# Isolation.net
KiCad netlist of a schematic drawn in Altium Designer
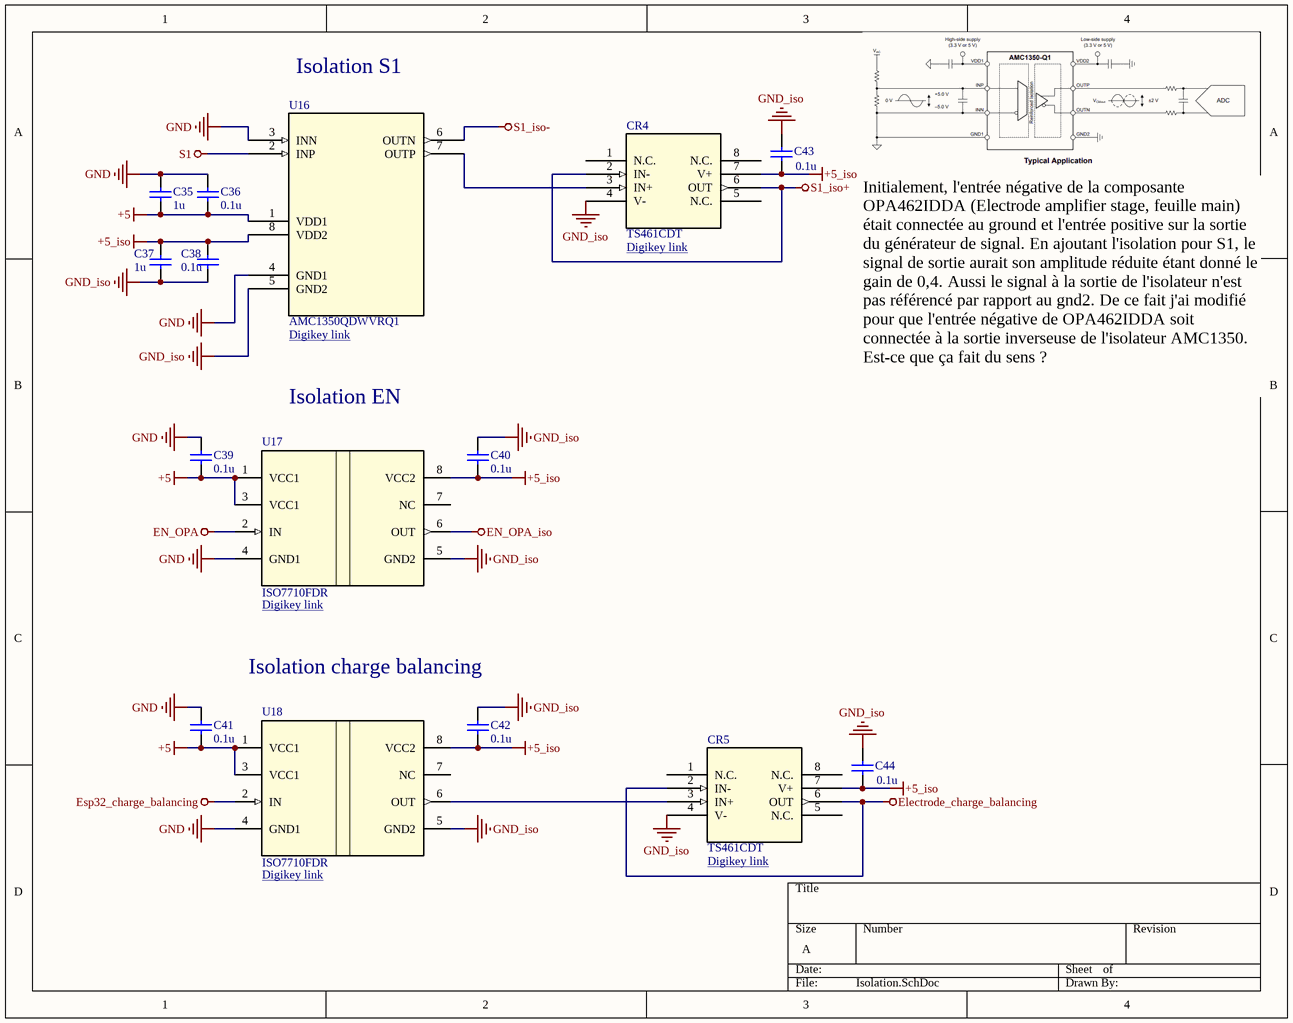
[diagram p0: Isolation.SchDoc]

(export (version "E")
  (design (tool "Eeschema 10.0.6"))
  (components
    (comp (ref "C35")
      (value "1u")
      (footprint "0805_AVX")
      (description "Capacitor")
      (libsource (lib "Simulation Generic Components") (part "Capacitor"))
    )
    (comp (ref "C36")
      (value "0.1u")
      (footprint "CAPC2012X150N")
      (description "Capacitor")
      (libsource (lib "Simulation Generic Components") (part "Capacitor"))
    )
    (comp (ref "C37")
      (value "1u")
      (footprint "0805_AVX")
      (description "Capacitor")
      (libsource (lib "Simulation Generic Components") (part "Capacitor"))
    )
    (comp (ref "C38")
      (value "0.1u")
      (footprint "CAPC2012X150N")
      (description "Capacitor")
      (libsource (lib "Simulation Generic Components") (part "Capacitor"))
    )
    (comp (ref "C39")
      (value "0.1u")
      (footprint "CAPC2012X150N")
      (description "Capacitor")
      (libsource (lib "Simulation Generic Components") (part "Capacitor"))
    )
    (comp (ref "C40")
      (value "0.1u")
      (footprint "CAPC2012X150N")
      (description "Capacitor")
      (libsource (lib "Simulation Generic Components") (part "Capacitor"))
    )
    (comp (ref "C41")
      (value "0.1u")
      (footprint "CAPC2012X150N")
      (description "Capacitor")
      (libsource (lib "Simulation Generic Components") (part "Capacitor"))
    )
    (comp (ref "C42")
      (value "0.1u")
      (footprint "CAPC2012X150N")
      (description "Capacitor")
      (libsource (lib "Simulation Generic Components") (part "Capacitor"))
    )
    (comp (ref "C43")
      (value "0.1u")
      (footprint "CAPC2012X150N")
      (description "Capacitor")
      (libsource (lib "Simulation Generic Components") (part "Capacitor"))
    )
    (comp (ref "C44")
      (value "0.1u")
      (footprint "CAPC2012X150N")
      (description "Capacitor")
      (libsource (lib "Simulation Generic Components") (part "Capacitor"))
    )
    (comp (ref "CR4")
      (value "TS461CDT")
      (footprint "SO-8_STM")
      (description "Output rail-to-rail op-amps")
      (fields (field (name "COPYRIGHT") "Copyright (C) 2026 Ultra Librarian. All rights reserved."))
      (libsource (lib "TS461CDT") (part "TS461CDT"))
    )
    (comp (ref "CR5")
      (value "TS461CDT")
      (footprint "SO-8_STM")
      (description "Output rail-to-rail op-amps")
      (fields (field (name "COPYRIGHT") "Copyright (C) 2026 Ultra Librarian. All rights reserved."))
      (libsource (lib "TS461CDT") (part "TS461CDT"))
    )
    (comp (ref "U16")
      (value "AMC1350QDWVRQ1")
      (footprint "AMC1350QDWVRQ1_TEX")
      (fields (field (name "COPYRIGHT") "Copyright (C) 2026 Ultra Librarian. All rights reserved."))
      (libsource (lib "AMC1350QDWVRQ1") (part "AMC1350QDWVRQ1"))
    )
    (comp (ref "U17")
      (value "ISO7710FDR")
      (footprint "D0008B_N")
      (description "Robust EMC, single-channel, reinforced digital isolator 8-SOIC -55 to 125")
      (fields (field (name "COPYRIGHT") "Copyright (C) 2026 Ultra Librarian. All rights reserved."))
      (libsource (lib "ISO7710FDR") (part "ISO7710FDR"))
    )
    (comp (ref "U18")
      (value "ISO7710FDR")
      (footprint "D0008B_N")
      (description "Robust EMC, single-channel, reinforced digital isolator 8-SOIC -55 to 125")
      (fields (field (name "COPYRIGHT") "Copyright (C) 2026 Ultra Librarian. All rights reserved."))
      (libsource (lib "ISO7710FDR") (part "ISO7710FDR"))
    )
  )
  (nets
    (net (code "1") (name "+5") (class "Default")
      (node (ref "C35") (pin "2") (pinfunction "2_2") (pintype "passive"))
      (node (ref "C36") (pin "1") (pinfunction "1_1") (pintype "passive"))
      (node (ref "C39") (pin "2") (pinfunction "2_2") (pintype "passive"))
      (node (ref "C41") (pin "2") (pinfunction "2_2") (pintype "passive"))
      (node (ref "U16") (pin "1") (pinfunction "VDD1_1") (pintype "power_in"))
      (node (ref "U17") (pin "1") (pinfunction "VCC1_1") (pintype "power_in"))
      (node (ref "U17") (pin "3") (pinfunction "VCC1_3") (pintype "power_in"))
      (node (ref "U18") (pin "1") (pinfunction "VCC1_1") (pintype "power_in"))
      (node (ref "U18") (pin "3") (pinfunction "VCC1_3") (pintype "power_in"))
    )
    (net (code "2") (name "+5_iso") (class "Default")
      (node (ref "C37") (pin "1") (pinfunction "1_1") (pintype "passive"))
      (node (ref "C38") (pin "2") (pinfunction "2_2") (pintype "passive"))
      (node (ref "C40") (pin "2") (pinfunction "2_2") (pintype "passive"))
      (node (ref "C42") (pin "2") (pinfunction "2_2") (pintype "passive"))
      (node (ref "C43") (pin "2") (pinfunction "2_2") (pintype "passive"))
      (node (ref "C44") (pin "2") (pinfunction "2_2") (pintype "passive"))
      (node (ref "CR4") (pin "7") (pinfunction "V+_7") (pintype "power_in"))
      (node (ref "CR5") (pin "7") (pinfunction "V+_7") (pintype "power_in"))
      (node (ref "U16") (pin "8") (pinfunction "VDD2_8") (pintype "power_in"))
      (node (ref "U17") (pin "8") (pinfunction "VCC2_8") (pintype "power_in"))
      (node (ref "U18") (pin "8") (pinfunction "VCC2_8") (pintype "power_in"))
    )
    (net (code "3") (name "EN_OPA") (class "Default")
      (node (ref "U17") (pin "2") (pinfunction "IN_2") (pintype "input"))
    )
    (net (code "4") (name "EN_OPA_iso") (class "Default")
      (node (ref "U17") (pin "6") (pinfunction "OUT_6") (pintype "output"))
    )
    (net (code "5") (name "Electrode_charge_balancing") (class "Default")
      (node (ref "CR5") (pin "2") (pinfunction "IN-_2") (pintype "input"))
      (node (ref "CR5") (pin "6") (pinfunction "OUT_6") (pintype "output"))
    )
    (net (code "6") (name "Esp32_charge_balancing") (class "Default")
      (node (ref "U18") (pin "2") (pinfunction "IN_2") (pintype "input"))
    )
    (net (code "7") (name "GND") (class "Default")
      (node (ref "C35") (pin "1") (pinfunction "1_1") (pintype "passive"))
      (node (ref "C36") (pin "2") (pinfunction "2_2") (pintype "passive"))
      (node (ref "C39") (pin "1") (pinfunction "1_1") (pintype "passive"))
      (node (ref "C41") (pin "1") (pinfunction "1_1") (pintype "passive"))
      (node (ref "U16") (pin "3") (pinfunction "INN_3") (pintype "input"))
      (node (ref "U16") (pin "4") (pinfunction "GND1_4") (pintype "power_in"))
      (node (ref "U17") (pin "4") (pinfunction "GND1_4") (pintype "power_in"))
      (node (ref "U18") (pin "4") (pinfunction "GND1_4") (pintype "power_in"))
    )
    (net (code "8") (name "GND_iso") (class "Default")
      (node (ref "C37") (pin "2") (pinfunction "2_2") (pintype "passive"))
      (node (ref "C38") (pin "1") (pinfunction "1_1") (pintype "passive"))
      (node (ref "C40") (pin "1") (pinfunction "1_1") (pintype "passive"))
      (node (ref "C42") (pin "1") (pinfunction "1_1") (pintype "passive"))
      (node (ref "C43") (pin "1") (pinfunction "1_1") (pintype "passive"))
      (node (ref "C44") (pin "1") (pinfunction "1_1") (pintype "passive"))
      (node (ref "CR4") (pin "4") (pinfunction "V-_4") (pintype "power_in"))
      (node (ref "CR5") (pin "4") (pinfunction "V-_4") (pintype "power_in"))
      (node (ref "U16") (pin "5") (pinfunction "GND2_5") (pintype "power_in"))
      (node (ref "U17") (pin "5") (pinfunction "GND2_5") (pintype "power_in"))
      (node (ref "U18") (pin "5") (pinfunction "GND2_5") (pintype "power_in"))
    )
    (net (code "9") (name "Net-(CR4-IN+)") (class "Default")
      (node (ref "CR4") (pin "3") (pinfunction "IN+_3") (pintype "input"))
      (node (ref "U16") (pin "7") (pinfunction "OUTP_7") (pintype "output"))
    )
    (net (code "10") (name "Net-(CR5-IN+)") (class "Default")
      (node (ref "CR5") (pin "3") (pinfunction "IN+_3") (pintype "input"))
      (node (ref "U18") (pin "6") (pinfunction "OUT_6") (pintype "output"))
    )
    (net (code "11") (name "S1") (class "Default")
      (node (ref "U16") (pin "2") (pinfunction "INP_2") (pintype "input"))
    )
    (net (code "12") (name "S1_iso+") (class "Default")
      (node (ref "CR4") (pin "2") (pinfunction "IN-_2") (pintype "input"))
      (node (ref "CR4") (pin "6") (pinfunction "OUT_6") (pintype "output"))
    )
    (net (code "13") (name "S1_iso-") (class "Default")
      (node (ref "U16") (pin "6") (pinfunction "OUTN_6") (pintype "output"))
    )
    (net (code "14") (name "unconnected-(CR4-N.C.-Pad1)") (class "Default")
      (node (ref "CR4") (pin "1") (pinfunction "N.C._1") (pintype "passive"))
    )
    (net (code "15") (name "unconnected-(CR4-N.C.-Pad5)") (class "Default")
      (node (ref "CR4") (pin "5") (pinfunction "N.C._5") (pintype "passive"))
    )
    (net (code "16") (name "unconnected-(CR4-N.C.-Pad8)") (class "Default")
      (node (ref "CR4") (pin "8") (pinfunction "N.C._8") (pintype "passive"))
    )
    (net (code "17") (name "unconnected-(CR5-N.C.-Pad1)") (class "Default")
      (node (ref "CR5") (pin "1") (pinfunction "N.C._1") (pintype "passive"))
    )
    (net (code "18") (name "unconnected-(CR5-N.C.-Pad5)") (class "Default")
      (node (ref "CR5") (pin "5") (pinfunction "N.C._5") (pintype "passive"))
    )
    (net (code "19") (name "unconnected-(CR5-N.C.-Pad8)") (class "Default")
      (node (ref "CR5") (pin "8") (pinfunction "N.C._8") (pintype "passive"))
    )
    (net (code "20") (name "unconnected-(U17-NC-Pad7)") (class "Default")
      (node (ref "U17") (pin "7") (pinfunction "NC_7") (pintype "passive"))
    )
    (net (code "21") (name "unconnected-(U18-NC-Pad7)") (class "Default")
      (node (ref "U18") (pin "7") (pinfunction "NC_7") (pintype "passive"))
    )
  )
)
